# raspi3_nonHatv3.net
KiCad netlist of a schematic drawn in EAGLE
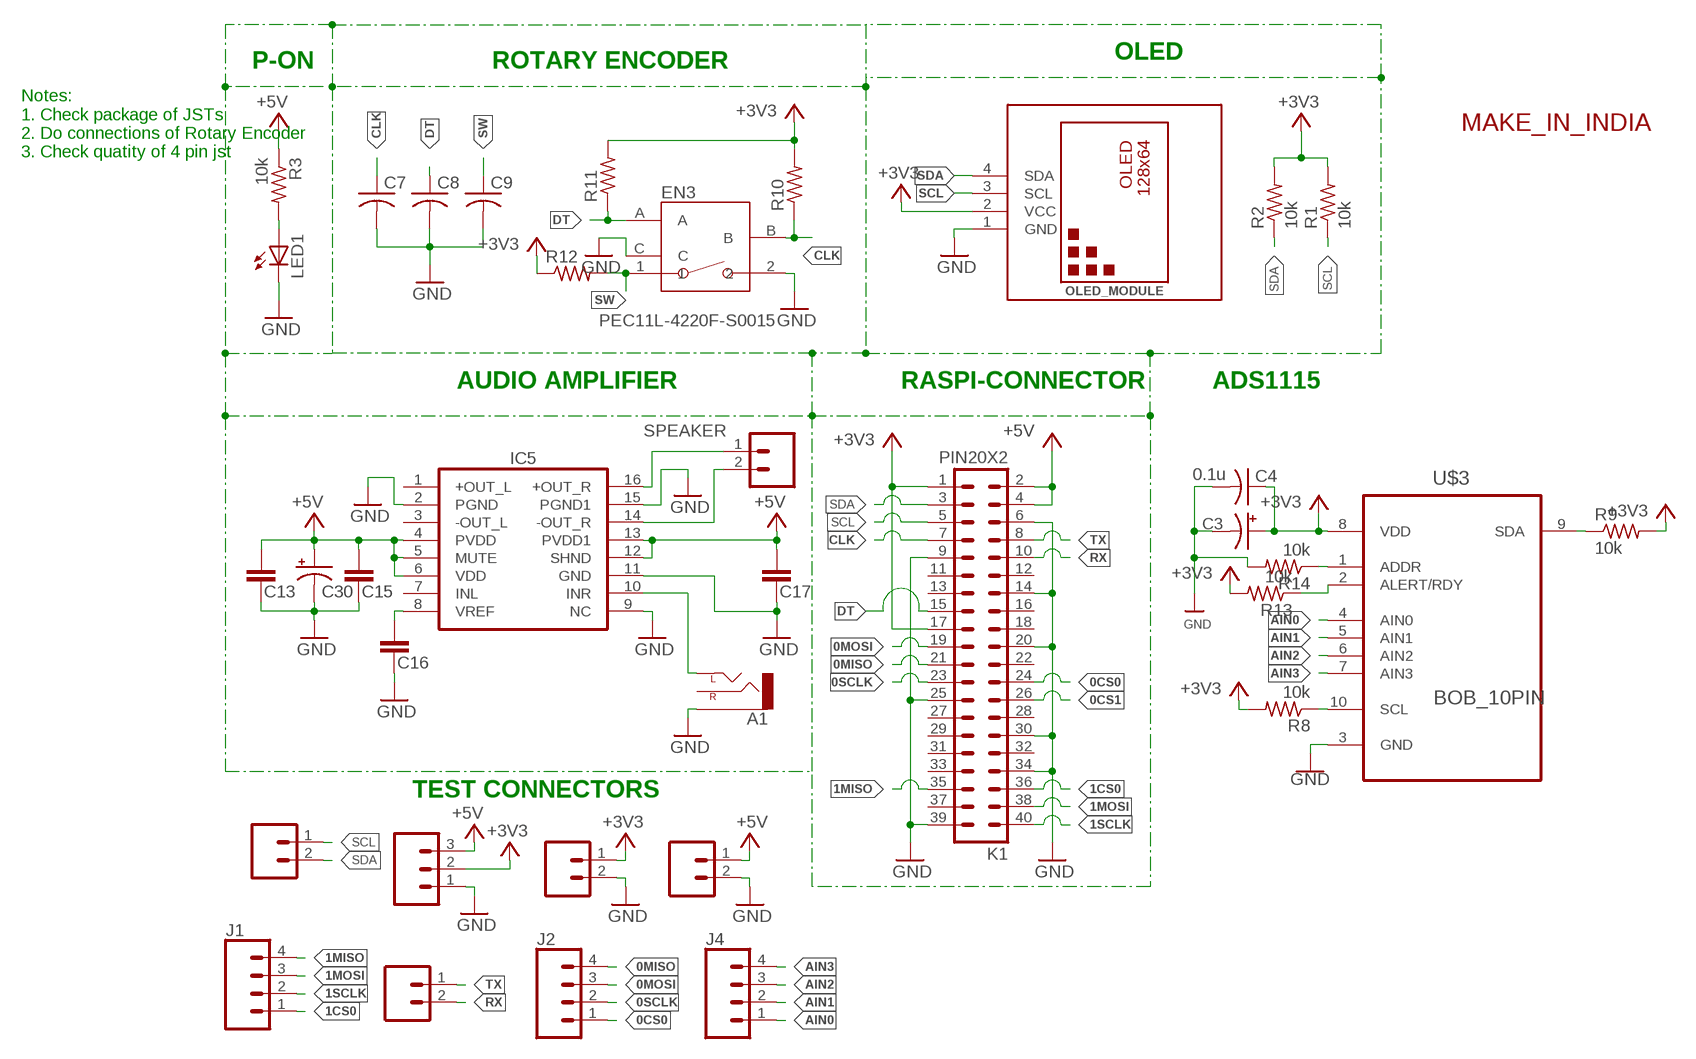
[diagram p0: schematic, sheet 1]

(export (version "E")
  (design (tool "Eeschema 10.0.6"))
  (components
    (comp (ref "A1")
      (value "AUDIO-JACKPTH")
      (footprint "eagle-import:AUDIO-JACK")
      (libsource (lib "eagle-import") (part "AUDIO-JACKPTH"))
    )
    (comp (ref "C3")
      (value "10u")
      (footprint "eagle-import:C_6032-28R")
      (libsource (lib "eagle-import") (part "CAP_POL_10V"))
    )
    (comp (ref "C4")
      (value "0.1u")
      (footprint "eagle-import:C0805")
      (libsource (lib "eagle-import") (part "CAP0805"))
    )
    (comp (ref "C7")
      (value "C-USC0603K")
      (footprint "eagle-import:C0603K")
      (libsource (lib "eagle-import") (part "C-USC0603K"))
    )
    (comp (ref "C8")
      (value "C-USC0603K")
      (footprint "eagle-import:C0603K")
      (libsource (lib "eagle-import") (part "C-USC0603K"))
    )
    (comp (ref "C9")
      (value "C-USC0603K")
      (footprint "eagle-import:C0603K")
      (libsource (lib "eagle-import") (part "C-USC0603K"))
    )
    (comp (ref "C13")
      (value "1uf")
      (footprint "eagle-import:C1206")
      (libsource (lib "eagle-import") (part "C-EUC1206"))
    )
    (comp (ref "C15")
      (value "1uf")
      (footprint "eagle-import:C1206")
      (libsource (lib "eagle-import") (part "C-EUC1206"))
    )
    (comp (ref "C16")
      (value "0.1uf")
      (footprint "eagle-import:C1206")
      (libsource (lib "eagle-import") (part "C-EUC1206"))
    )
    (comp (ref "C17")
      (value "1uf")
      (footprint "eagle-import:C1206")
      (libsource (lib "eagle-import") (part "C-EUC1206"))
    )
    (comp (ref "C30")
      (value "CAP_POL_10V")
      (footprint "eagle-import:C_6032-28R")
      (libsource (lib "eagle-import") (part "CEDT_SEPTEMBER_V2_CAP_POL_10V"))
    )
    (comp (ref "EN3")
      (value "PEC11L-4220F-S0015")
      (footprint "eagle-import:PEC11L-4220F-S0015")
      (fields
        (field (name "DIGIKEY_PARTNO") "PEC11L-4220F-S0015-ND")
        (field (name "MANUFACTURER") "Bourns Inc.")
        (field (name "CREATED_BY") "PCBLayout.com")
      )
      (libsource (lib "eagle-import") (part "PEC11L-4220F-S0015"))
    )
    (comp (ref "IC5")
      (value "PAM8403")
      (footprint "eagle-import:SOP-16")
      (libsource (lib "eagle-import") (part "PAM8403"))
    )
    (comp (ref "J1")
      (value "CONN_04POLAR")
      (footprint "eagle-import:MOLEX-1X4")
      (libsource (lib "eagle-import") (part "CONN_04POLAR"))
    )
    (comp (ref "J2")
      (value "CONN_04POLAR")
      (footprint "eagle-import:MOLEX-1X4")
      (libsource (lib "eagle-import") (part "CONN_04POLAR"))
    )
    (comp (ref "J4")
      (value "CONN_04POLAR")
      (footprint "eagle-import:MOLEX-1X4")
      (libsource (lib "eagle-import") (part "CONN_04POLAR"))
    )
    (comp (ref "K1")
      (value "PIN20X2")
      (footprint "eagle-import:PIN_20X2")
      (libsource (lib "eagle-import") (part "PIN20X2"))
    )
    (comp (ref "LED1")
      (value "LED3MM")
      (footprint "eagle-import:LED3MM")
      (libsource (lib "eagle-import") (part "LED3MM"))
    )
    (comp (ref "OLED_MODULE")
      (value "DIY-MODULES_DISPLAY-OLED-128X64-I2C")
      (footprint "eagle-import:DIY-MODULES_DISPLAY-OLED-128X64-I2C")
      (libsource (lib "eagle-import") (part "DIY-MODULES_DISPLAY-OLED-128X64-I2C"))
    )
    (comp (ref "POWER")
      (value "CONN_03POLAR")
      (footprint "eagle-import:MOLEX-1X3")
      (libsource (lib "eagle-import") (part "CONN_03POLAR"))
    )
    (comp (ref "R1")
      (value "10k")
      (footprint "eagle-import:0207_7")
      (libsource (lib "eagle-import") (part "RESISTOR0207/7"))
    )
    (comp (ref "R2")
      (value "10k")
      (footprint "eagle-import:0207_7")
      (libsource (lib "eagle-import") (part "RESISTOR0207/7"))
    )
    (comp (ref "R3")
      (value "10k")
      (footprint "eagle-import:0207_7")
      (libsource (lib "eagle-import") (part "RESISTOR0207/7"))
    )
    (comp (ref "R8")
      (value "10k")
      (footprint "eagle-import:R0603")
      (libsource (lib "eagle-import") (part "CEDT_JANUARY_2015_v5_RESISTOR0603"))
    )
    (comp (ref "R9")
      (value "10k")
      (footprint "eagle-import:R0603")
      (libsource (lib "eagle-import") (part "CEDT_JANUARY_2015_v5_RESISTOR0603"))
    )
    (comp (ref "R10")
      (value "R-US_M0805")
      (footprint "eagle-import:M0805")
      (libsource (lib "eagle-import") (part "R-US_M0805"))
    )
    (comp (ref "R11")
      (value "R-US_M0805")
      (footprint "eagle-import:M0805")
      (libsource (lib "eagle-import") (part "R-US_M0805"))
    )
    (comp (ref "R12")
      (value "R-US_M0805")
      (footprint "eagle-import:M0805")
      (libsource (lib "eagle-import") (part "R-US_M0805"))
    )
    (comp (ref "R13")
      (value "10k")
      (footprint "eagle-import:R0603")
      (libsource (lib "eagle-import") (part "CEDT_JANUARY_2015_v5_RESISTOR0603"))
    )
    (comp (ref "R14")
      (value "10k")
      (footprint "eagle-import:R0603")
      (libsource (lib "eagle-import") (part "CEDT_JANUARY_2015_v5_RESISTOR0603"))
    )
    (comp (ref "SPEAKER")
      (value "M02")
      (footprint "eagle-import:02P")
      (libsource (lib "eagle-import") (part "M02"))
    )
    (comp (ref "THERMISTOR1")
      (value "CONN_02POLAR")
      (footprint "eagle-import:MOLEX-1X2")
      (libsource (lib "eagle-import") (part "CONN_02POLAR"))
    )
    (comp (ref "THERMISTOR2")
      (value "CONN_02POLAR")
      (footprint "eagle-import:MOLEX-1X2")
      (libsource (lib "eagle-import") (part "CONN_02POLAR"))
    )
    (comp (ref "THERMISTOR3")
      (value "CONN_02POLAR")
      (footprint "eagle-import:MOLEX-1X2")
      (libsource (lib "eagle-import") (part "CONN_02POLAR"))
    )
    (comp (ref "THERMISTOR4")
      (value "CONN_02POLAR")
      (footprint "eagle-import:MOLEX-1X2")
      (libsource (lib "eagle-import") (part "CONN_02POLAR"))
    )
    (comp (ref "U$1")
      (value "MAKE-IN-INDIA-LOGO")
      (footprint "eagle-import:MAKE-IN-INDIA")
      (libsource (lib "eagle-import") (part "MAKE-IN-INDIA-LOGO"))
    )
    (comp (ref "U$3")
      (value "BOB_10PIN")
      (footprint "eagle-import:BOB10")
      (libsource (lib "eagle-import") (part "BOB_10PIN"))
    )
  )
  (nets
    (net (code "1") (name "+3V3") (class "Default")
      (node (ref "C3") (pin "+") (pinfunction "+_+") (pintype "passive"))
      (node (ref "C4") (pin "1") (pinfunction "1_1") (pintype "passive"))
      (node (ref "K1") (pin "1") (pinfunction "1_1") (pintype "passive"))
      (node (ref "K1") (pin "17") (pinfunction "17_17") (pintype "passive"))
      (node (ref "OLED_MODULE") (pin "2") (pinfunction "VCC_2") (pintype "power_in"))
      (node (ref "POWER") (pin "2") (pinfunction "2_2") (pintype "passive"))
      (node (ref "R1") (pin "2") (pinfunction "2_2") (pintype "passive"))
      (node (ref "R10") (pin "2") (pinfunction "2_2") (pintype "passive"))
      (node (ref "R11") (pin "2") (pinfunction "2_2") (pintype "passive"))
      (node (ref "R12") (pin "1") (pinfunction "1_1") (pintype "passive"))
      (node (ref "R13") (pin "2") (pinfunction "2_2") (pintype "passive"))
      (node (ref "R2") (pin "2") (pinfunction "2_2") (pintype "passive"))
      (node (ref "R8") (pin "2") (pinfunction "2_2") (pintype "passive"))
      (node (ref "R9") (pin "2") (pinfunction "2_2") (pintype "passive"))
      (node (ref "THERMISTOR2") (pin "1") (pinfunction "1_1") (pintype "passive"))
      (node (ref "U$3") (pin "8") (pinfunction "VDD_8") (pintype "power_in"))
    )
    (net (code "2") (name "+5V") (class "Default")
      (node (ref "C13") (pin "1") (pinfunction "1_1") (pintype "passive"))
      (node (ref "C15") (pin "2") (pinfunction "2_2") (pintype "passive"))
      (node (ref "C17") (pin "2") (pinfunction "2_2") (pintype "passive"))
      (node (ref "C30") (pin "+") (pinfunction "+_+") (pintype "passive"))
      (node (ref "IC5") (pin "12") (pinfunction "SHND_12") (pintype "output"))
      (node (ref "IC5") (pin "13") (pinfunction "PVDD1_13") (pintype "output"))
      (node (ref "IC5") (pin "4") (pinfunction "PVDD_4") (pintype "input"))
      (node (ref "IC5") (pin "5") (pinfunction "MUTE_5") (pintype "input"))
      (node (ref "IC5") (pin "6") (pinfunction "VDD_6") (pintype "input"))
      (node (ref "K1") (pin "2") (pinfunction "2_2") (pintype "passive"))
      (node (ref "K1") (pin "4") (pinfunction "4_4") (pintype "passive"))
      (node (ref "POWER") (pin "3") (pinfunction "3_3") (pintype "passive"))
      (node (ref "R3") (pin "1") (pinfunction "1_1") (pintype "passive"))
      (node (ref "THERMISTOR3") (pin "1") (pinfunction "1_1") (pintype "passive"))
    )
    (net (code "3") (name "0CS0") (class "Default")
      (node (ref "J2") (pin "1") (pinfunction "1_1") (pintype "passive"))
      (node (ref "K1") (pin "24") (pinfunction "24_24") (pintype "passive"))
    )
    (net (code "4") (name "0CS1") (class "Default")
      (node (ref "K1") (pin "26") (pinfunction "26_26") (pintype "passive"))
    )
    (net (code "5") (name "0MISO") (class "Default")
      (node (ref "J2") (pin "4") (pinfunction "4_4") (pintype "passive"))
      (node (ref "K1") (pin "21") (pinfunction "21_21") (pintype "passive"))
    )
    (net (code "6") (name "0MOSI") (class "Default")
      (node (ref "J2") (pin "3") (pinfunction "3_3") (pintype "passive"))
      (node (ref "K1") (pin "19") (pinfunction "19_19") (pintype "passive"))
    )
    (net (code "7") (name "0SCLK") (class "Default")
      (node (ref "J2") (pin "2") (pinfunction "2_2") (pintype "passive"))
      (node (ref "K1") (pin "23") (pinfunction "23_23") (pintype "passive"))
    )
    (net (code "8") (name "1CS0") (class "Default")
      (node (ref "J1") (pin "1") (pinfunction "1_1") (pintype "passive"))
      (node (ref "K1") (pin "36") (pinfunction "36_36") (pintype "passive"))
    )
    (net (code "9") (name "1MISO") (class "Default")
      (node (ref "J1") (pin "4") (pinfunction "4_4") (pintype "passive"))
      (node (ref "K1") (pin "35") (pinfunction "35_35") (pintype "passive"))
    )
    (net (code "10") (name "1MOSI") (class "Default")
      (node (ref "J1") (pin "3") (pinfunction "3_3") (pintype "passive"))
      (node (ref "K1") (pin "38") (pinfunction "38_38") (pintype "passive"))
    )
    (net (code "11") (name "1SCLK") (class "Default")
      (node (ref "J1") (pin "2") (pinfunction "2_2") (pintype "passive"))
      (node (ref "K1") (pin "40") (pinfunction "40_40") (pintype "passive"))
    )
    (net (code "12") (name "AIN0") (class "Default")
      (node (ref "J4") (pin "1") (pinfunction "1_1") (pintype "passive"))
      (node (ref "U$3") (pin "4") (pinfunction "AIN0_4") (pintype "input"))
    )
    (net (code "13") (name "AIN1") (class "Default")
      (node (ref "J4") (pin "2") (pinfunction "2_2") (pintype "passive"))
      (node (ref "U$3") (pin "5") (pinfunction "AIN1_5") (pintype "input"))
    )
    (net (code "14") (name "AIN2") (class "Default")
      (node (ref "J4") (pin "3") (pinfunction "3_3") (pintype "passive"))
      (node (ref "U$3") (pin "6") (pinfunction "AIN2_6") (pintype "input"))
    )
    (net (code "15") (name "AIN3") (class "Default")
      (node (ref "J4") (pin "4") (pinfunction "4_4") (pintype "passive"))
      (node (ref "U$3") (pin "7") (pinfunction "AIN3_7") (pintype "input"))
    )
    (net (code "16") (name "CLK") (class "Default")
      (node (ref "C7") (pin "1") (pinfunction "1_1") (pintype "passive"))
      (node (ref "EN3") (pin "B") (pinfunction "B_B") (pintype "passive"))
      (node (ref "K1") (pin "7") (pinfunction "7_7") (pintype "passive"))
      (node (ref "R10") (pin "1") (pinfunction "1_1") (pintype "passive"))
    )
    (net (code "17") (name "DT") (class "Default")
      (node (ref "C8") (pin "1") (pinfunction "1_1") (pintype "passive"))
      (node (ref "EN3") (pin "A") (pinfunction "A_A") (pintype "passive"))
      (node (ref "K1") (pin "15") (pinfunction "15_15") (pintype "passive"))
      (node (ref "R11") (pin "1") (pinfunction "1_1") (pintype "passive"))
    )
    (net (code "18") (name "GND") (class "Default")
      (node (ref "A1") (pin "SLEEVE") (pinfunction "SLEEVE_SLEEVE") (pintype "bidirectional"))
      (node (ref "C13") (pin "2") (pinfunction "2_2") (pintype "passive"))
      (node (ref "C15") (pin "1") (pinfunction "1_1") (pintype "passive"))
      (node (ref "C16") (pin "2") (pinfunction "2_2") (pintype "passive"))
      (node (ref "C17") (pin "1") (pinfunction "1_1") (pintype "passive"))
      (node (ref "C3") (pin "-") (pinfunction "-_-") (pintype "passive"))
      (node (ref "C30") (pin "-") (pinfunction "-_-") (pintype "passive"))
      (node (ref "C4") (pin "2") (pinfunction "2_2") (pintype "passive"))
      (node (ref "C7") (pin "2") (pinfunction "2_2") (pintype "passive"))
      (node (ref "C8") (pin "2") (pinfunction "2_2") (pintype "passive"))
      (node (ref "C9") (pin "2") (pinfunction "2_2") (pintype "passive"))
      (node (ref "EN3") (pin "2") (pinfunction "2_2") (pintype "passive"))
      (node (ref "EN3") (pin "C") (pinfunction "C_C") (pintype "passive"))
      (node (ref "IC5") (pin "11") (pinfunction "GND_11") (pintype "output"))
      (node (ref "IC5") (pin "15") (pinfunction "PGND1_15") (pintype "output"))
      (node (ref "IC5") (pin "2") (pinfunction "PGND_2") (pintype "input"))
      (node (ref "IC5") (pin "9") (pinfunction "NC_9") (pintype "output"))
      (node (ref "K1") (pin "14") (pinfunction "14_14") (pintype "passive"))
      (node (ref "K1") (pin "20") (pinfunction "20_20") (pintype "passive"))
      (node (ref "K1") (pin "25") (pinfunction "25_25") (pintype "passive"))
      (node (ref "K1") (pin "30") (pinfunction "30_30") (pintype "passive"))
      (node (ref "K1") (pin "34") (pinfunction "34_34") (pintype "passive"))
      (node (ref "K1") (pin "39") (pinfunction "39_39") (pintype "passive"))
      (node (ref "K1") (pin "6") (pinfunction "6_6") (pintype "passive"))
      (node (ref "K1") (pin "9") (pinfunction "9_9") (pintype "passive"))
      (node (ref "LED1") (pin "K") (pinfunction "C_K") (pintype "passive"))
      (node (ref "OLED_MODULE") (pin "1") (pinfunction "GND_1") (pintype "power_in"))
      (node (ref "POWER") (pin "1") (pinfunction "1_1") (pintype "passive"))
      (node (ref "R14") (pin "2") (pinfunction "2_2") (pintype "passive"))
      (node (ref "THERMISTOR2") (pin "2") (pinfunction "2_2") (pintype "passive"))
      (node (ref "THERMISTOR3") (pin "2") (pinfunction "2_2") (pintype "passive"))
      (node (ref "U$3") (pin "3") (pinfunction "GND_3") (pintype "passive"))
    )
    (net (code "19") (name "Net-(A1-LEFT)") (class "Default")
      (node (ref "A1") (pin "TIP") (pinfunction "LEFT_TIP") (pintype "bidirectional"))
      (node (ref "IC5") (pin "10") (pinfunction "INR_10") (pintype "output"))
    )
    (net (code "20") (name "Net-(IC5-+OUT_R)") (class "Default")
      (node (ref "IC5") (pin "16") (pinfunction "+OUT_R_16") (pintype "output"))
      (node (ref "SPEAKER") (pin "1") (pinfunction "1_1") (pintype "passive"))
    )
    (net (code "21") (name "Net-(IC5--OUT_R)") (class "Default")
      (node (ref "IC5") (pin "14") (pinfunction "-OUT_R_14") (pintype "output"))
      (node (ref "SPEAKER") (pin "2") (pinfunction "2_2") (pintype "passive"))
    )
    (net (code "22") (name "Net-(IC5-VREF)") (class "Default")
      (node (ref "C16") (pin "1") (pinfunction "1_1") (pintype "passive"))
      (node (ref "IC5") (pin "8") (pinfunction "VREF_8") (pintype "input"))
    )
    (net (code "23") (name "Net-(LED1-PadA)") (class "Default")
      (node (ref "LED1") (pin "A") (pinfunction "A_A") (pintype "passive"))
      (node (ref "R3") (pin "2") (pinfunction "2_2") (pintype "passive"))
    )
    (net (code "24") (name "Net-(U$3-ADDR)") (class "Default")
      (node (ref "R14") (pin "1") (pinfunction "1_1") (pintype "passive"))
      (node (ref "U$3") (pin "1") (pinfunction "ADDR_1") (pintype "input"))
    )
    (net (code "25") (name "Net-(U$3-ALERT{slash}RDY)") (class "Default")
      (node (ref "R13") (pin "1") (pinfunction "1_1") (pintype "passive"))
      (node (ref "U$3") (pin "2") (pinfunction "ALERT/RDY_2") (pintype "input"))
    )
    (net (code "26") (name "Net-(U$3-SCL)") (class "Default")
      (node (ref "R8") (pin "1") (pinfunction "1_1") (pintype "passive"))
      (node (ref "U$3") (pin "10") (pinfunction "SCL_10") (pintype "input"))
    )
    (net (code "27") (name "Net-(U$3-SDA)") (class "Default")
      (node (ref "R9") (pin "1") (pinfunction "1_1") (pintype "passive"))
      (node (ref "U$3") (pin "9") (pinfunction "SDA_9") (pintype "bidirectional"))
    )
    (net (code "28") (name "RX") (class "Default")
      (node (ref "K1") (pin "10") (pinfunction "10_10") (pintype "passive"))
      (node (ref "THERMISTOR4") (pin "2") (pinfunction "2_2") (pintype "passive"))
    )
    (net (code "29") (name "SCL") (class "Default")
      (node (ref "K1") (pin "5") (pinfunction "5_5") (pintype "passive"))
      (node (ref "OLED_MODULE") (pin "3") (pinfunction "SCL_3") (pintype "bidirectional"))
      (node (ref "R1") (pin "1") (pinfunction "1_1") (pintype "passive"))
      (node (ref "THERMISTOR1") (pin "1") (pinfunction "1_1") (pintype "passive"))
    )
    (net (code "30") (name "SDA") (class "Default")
      (node (ref "K1") (pin "3") (pinfunction "3_3") (pintype "passive"))
      (node (ref "OLED_MODULE") (pin "4") (pinfunction "SDA_4") (pintype "bidirectional"))
      (node (ref "R2") (pin "1") (pinfunction "1_1") (pintype "passive"))
      (node (ref "THERMISTOR1") (pin "2") (pinfunction "2_2") (pintype "passive"))
    )
    (net (code "31") (name "SW") (class "Default")
      (node (ref "C9") (pin "1") (pinfunction "1_1") (pintype "passive"))
      (node (ref "EN3") (pin "1") (pinfunction "1_1") (pintype "passive"))
      (node (ref "R12") (pin "2") (pinfunction "2_2") (pintype "passive"))
    )
    (net (code "32") (name "TX") (class "Default")
      (node (ref "K1") (pin "8") (pinfunction "8_8") (pintype "passive"))
      (node (ref "THERMISTOR4") (pin "1") (pinfunction "1_1") (pintype "passive"))
    )
    (net (code "33") (name "unconnected-(A1-RIGHT-PadRING)") (class "Default")
      (node (ref "A1") (pin "RING") (pinfunction "RIGHT_RING") (pintype "bidirectional"))
    )
    (net (code "34") (name "unconnected-(IC5-+OUT_L-Pad1)") (class "Default")
      (node (ref "IC5") (pin "1") (pinfunction "+OUT_L_1") (pintype "input"))
    )
    (net (code "35") (name "unconnected-(IC5--OUT_L-Pad3)") (class "Default")
      (node (ref "IC5") (pin "3") (pinfunction "-OUT_L_3") (pintype "input"))
    )
    (net (code "36") (name "unconnected-(IC5-INL-Pad7)") (class "Default")
      (node (ref "IC5") (pin "7") (pinfunction "INL_7") (pintype "input"))
    )
    (net (code "37") (name "unconnected-(K1-Pad11)") (class "Default")
      (node (ref "K1") (pin "11") (pinfunction "11_11") (pintype "passive"))
    )
    (net (code "38") (name "unconnected-(K1-Pad12)") (class "Default")
      (node (ref "K1") (pin "12") (pinfunction "12_12") (pintype "passive"))
    )
    (net (code "39") (name "unconnected-(K1-Pad13)") (class "Default")
      (node (ref "K1") (pin "13") (pinfunction "13_13") (pintype "passive"))
    )
    (net (code "40") (name "unconnected-(K1-Pad16)") (class "Default")
      (node (ref "K1") (pin "16") (pinfunction "16_16") (pintype "passive"))
    )
    (net (code "41") (name "unconnected-(K1-Pad18)") (class "Default")
      (node (ref "K1") (pin "18") (pinfunction "18_18") (pintype "passive"))
    )
    (net (code "42") (name "unconnected-(K1-Pad22)") (class "Default")
      (node (ref "K1") (pin "22") (pinfunction "22_22") (pintype "passive"))
    )
    (net (code "43") (name "unconnected-(K1-Pad27)") (class "Default")
      (node (ref "K1") (pin "27") (pinfunction "27_27") (pintype "passive"))
    )
    (net (code "44") (name "unconnected-(K1-Pad28)") (class "Default")
      (node (ref "K1") (pin "28") (pinfunction "28_28") (pintype "passive"))
    )
    (net (code "45") (name "unconnected-(K1-Pad29)") (class "Default")
      (node (ref "K1") (pin "29") (pinfunction "29_29") (pintype "passive"))
    )
    (net (code "46") (name "unconnected-(K1-Pad31)") (class "Default")
      (node (ref "K1") (pin "31") (pinfunction "31_31") (pintype "passive"))
    )
    (net (code "47") (name "unconnected-(K1-Pad32)") (class "Default")
      (node (ref "K1") (pin "32") (pinfunction "32_32") (pintype "passive"))
    )
    (net (code "48") (name "unconnected-(K1-Pad33)") (class "Default")
      (node (ref "K1") (pin "33") (pinfunction "33_33") (pintype "passive"))
    )
    (net (code "49") (name "unconnected-(K1-Pad37)") (class "Default")
      (node (ref "K1") (pin "37") (pinfunction "37_37") (pintype "passive"))
    )
  )
)
